# pcb-bldc-high-current.net
KiCad netlist of a schematic drawn in EAGLE
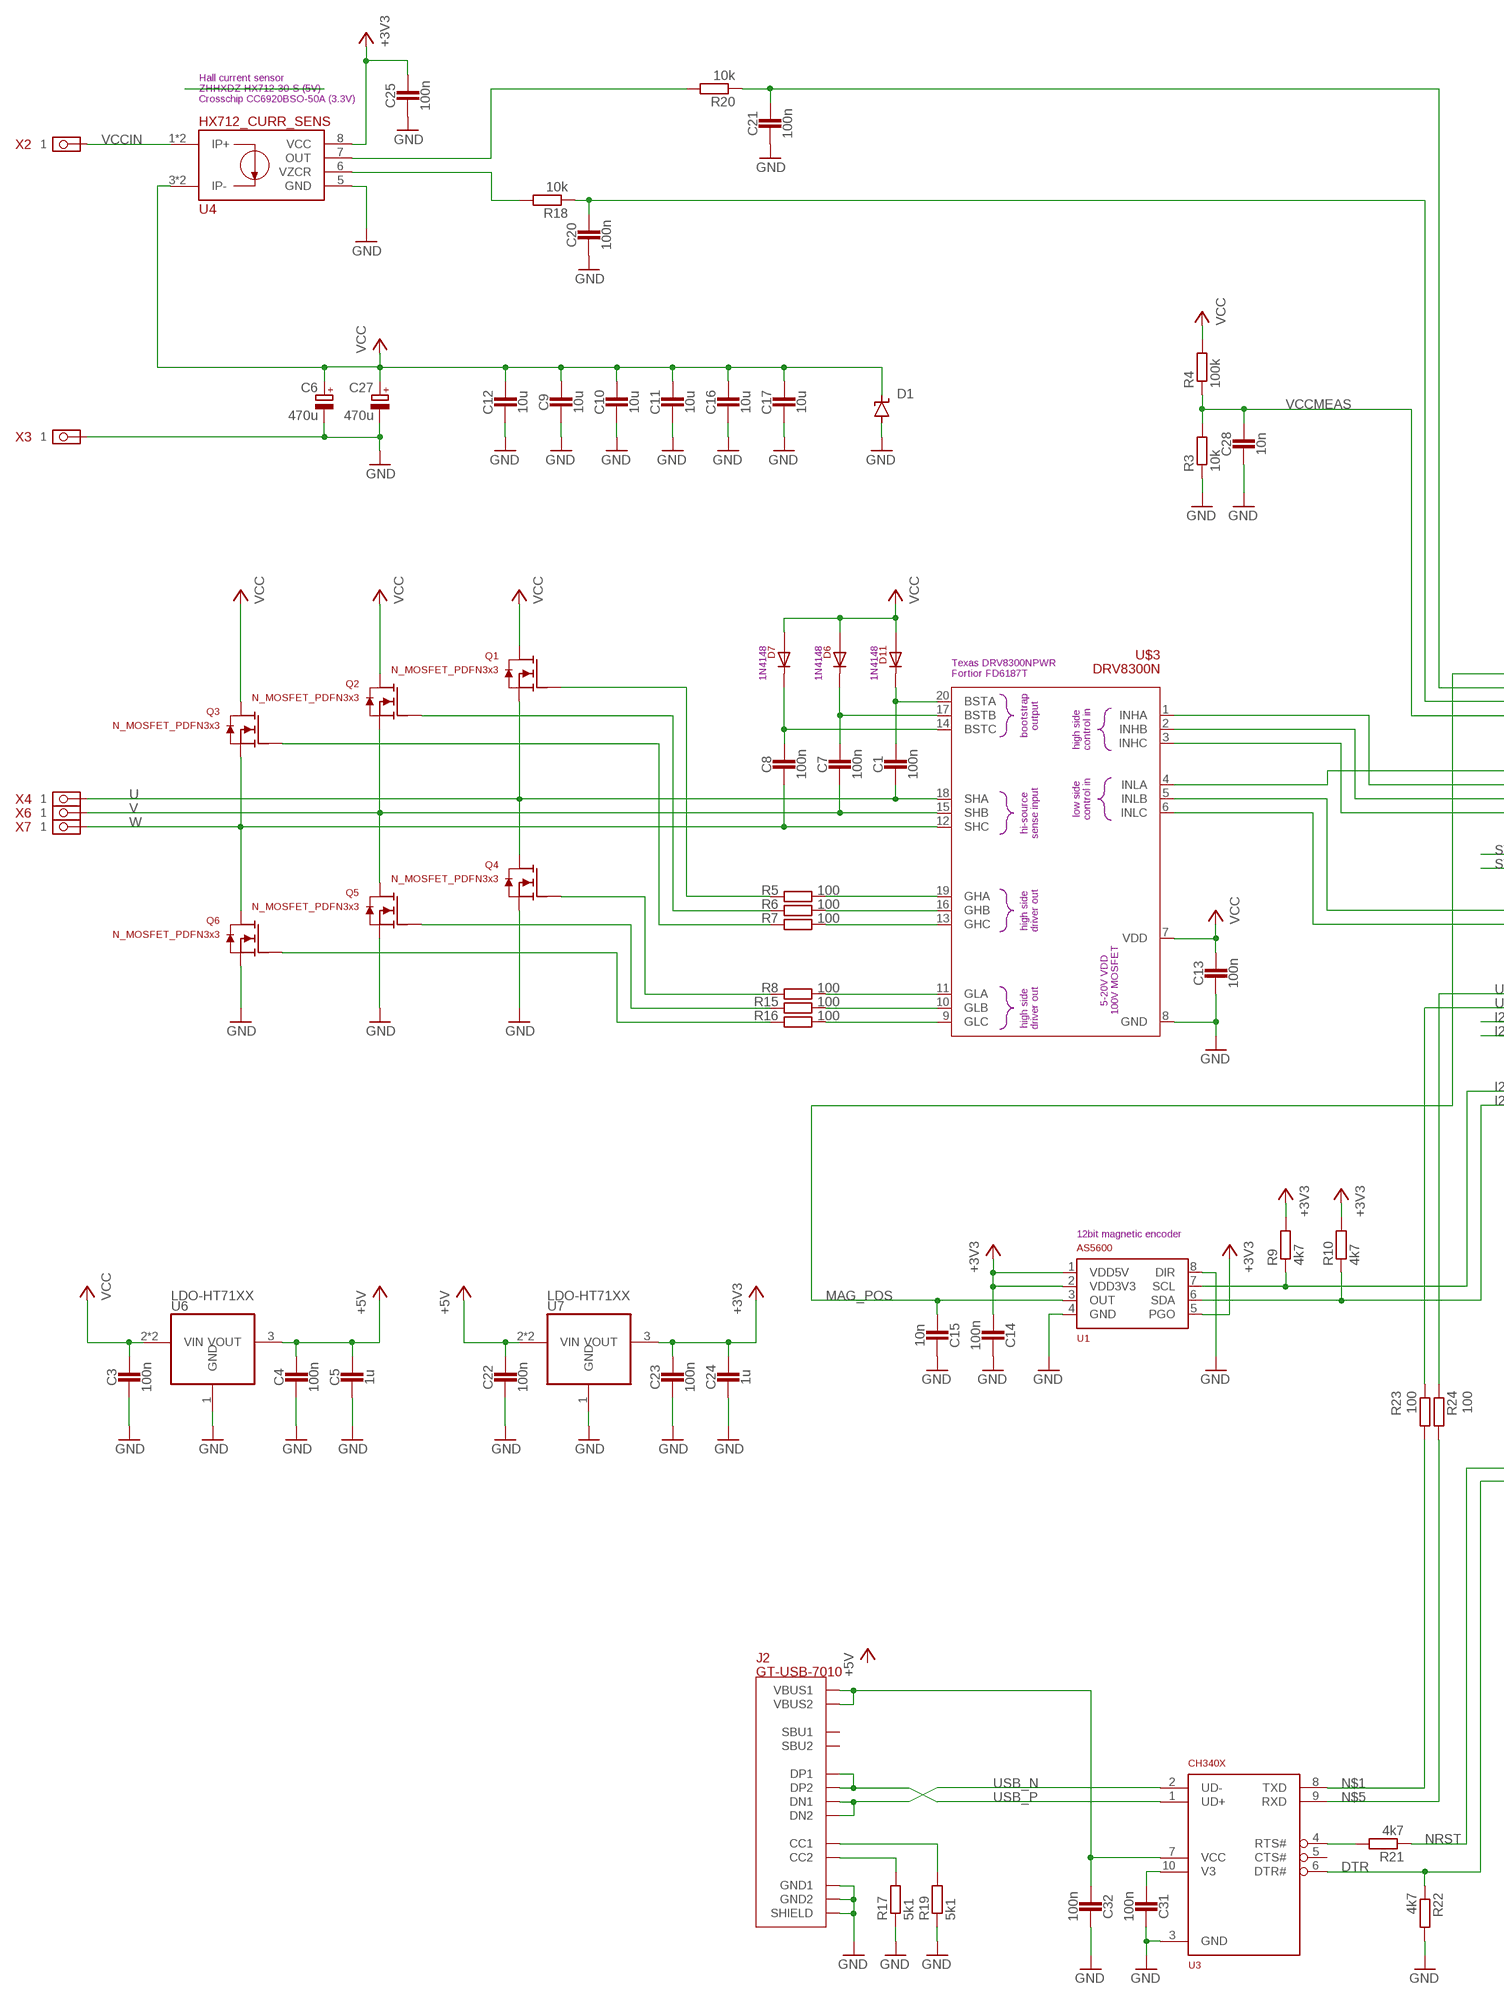
[diagram p0: schematic, sheet 1, part 1 of 2]
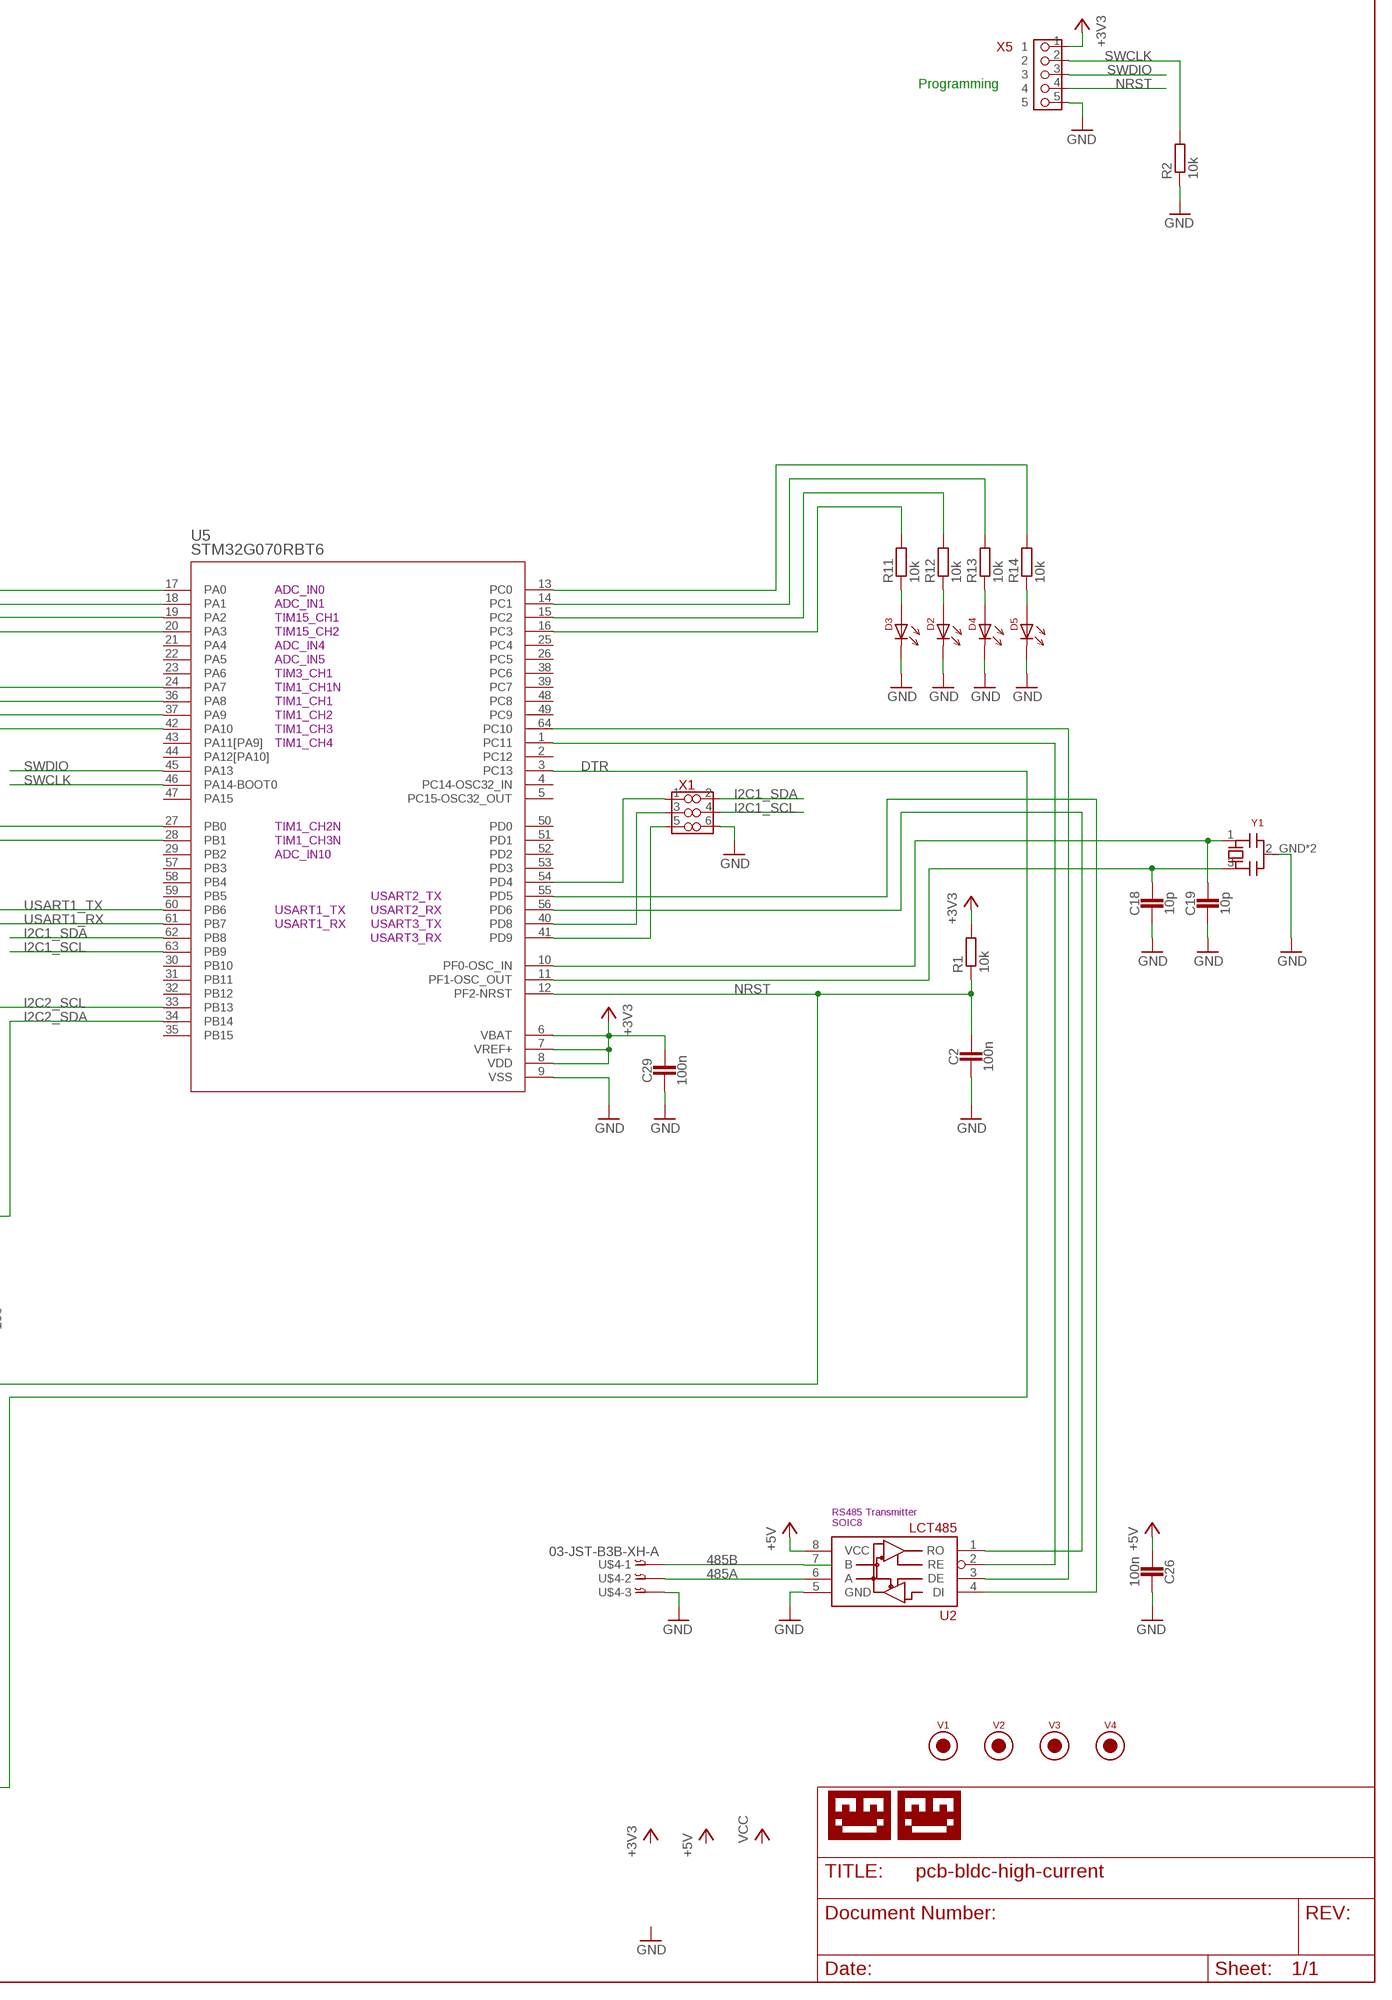
[diagram p1: schematic, sheet 1, part 2 of 2]

(export (version "E")
  (design (tool "Eeschema 10.0.6"))
  (components
    (comp (ref "C1")
      (value "100n")
      (footprint "eagle-import:0603_CAP")
      (libsource (lib "eagle-import") (part "CAPACITOR0603_CAP"))
    )
    (comp (ref "C2")
      (value "100n")
      (footprint "eagle-import:0603_CAP")
      (libsource (lib "eagle-import") (part "CAPACITOR0603_CAP"))
    )
    (comp (ref "C3")
      (value "100n")
      (footprint "eagle-import:0603_CAP")
      (libsource (lib "eagle-import") (part "CAPACITOR0603_CAP"))
    )
    (comp (ref "C4")
      (value "100n")
      (footprint "eagle-import:0603_CAP")
      (libsource (lib "eagle-import") (part "CAPACITOR0603_CAP"))
    )
    (comp (ref "C5")
      (value "1u")
      (footprint "eagle-import:0603_CAP")
      (libsource (lib "eagle-import") (part "CAPACITOR0603_CAP"))
    )
    (comp (ref "C6")
      (value "470u")
      (footprint "eagle-import:153CLV-1010")
      (libsource (lib "eagle-import") (part "CPOL-EU153CLV-1010"))
    )
    (comp (ref "C7")
      (value "100n")
      (footprint "eagle-import:0603_CAP")
      (libsource (lib "eagle-import") (part "CAPACITOR0603_CAP"))
    )
    (comp (ref "C8")
      (value "100n")
      (footprint "eagle-import:0603_CAP")
      (libsource (lib "eagle-import") (part "CAPACITOR0603_CAP"))
    )
    (comp (ref "C9")
      (value "10u")
      (footprint "eagle-import:1206_CAP")
      (libsource (lib "eagle-import") (part "CAPACITOR1206_CAP"))
    )
    (comp (ref "C10")
      (value "10u")
      (footprint "eagle-import:1206_CAP")
      (libsource (lib "eagle-import") (part "CAPACITOR1206_CAP"))
    )
    (comp (ref "C11")
      (value "10u")
      (footprint "eagle-import:1206_CAP")
      (libsource (lib "eagle-import") (part "CAPACITOR1206_CAP"))
    )
    (comp (ref "C12")
      (value "10u")
      (footprint "eagle-import:1206_CAP")
      (libsource (lib "eagle-import") (part "CAPACITOR1206_CAP"))
    )
    (comp (ref "C13")
      (value "100n")
      (footprint "eagle-import:0603_CAP")
      (libsource (lib "eagle-import") (part "CAPACITOR0603_CAP"))
    )
    (comp (ref "C14")
      (value "100n")
      (footprint "eagle-import:0603_CAP")
      (libsource (lib "eagle-import") (part "CAPACITOR0603_CAP"))
    )
    (comp (ref "C15")
      (value "10n")
      (footprint "eagle-import:0603_CAP")
      (libsource (lib "eagle-import") (part "CAPACITOR0603_CAP"))
    )
    (comp (ref "C16")
      (value "10u")
      (footprint "eagle-import:1206_CAP")
      (libsource (lib "eagle-import") (part "CAPACITOR1206_CAP"))
    )
    (comp (ref "C17")
      (value "10u")
      (footprint "eagle-import:1206_CAP")
      (libsource (lib "eagle-import") (part "CAPACITOR1206_CAP"))
    )
    (comp (ref "C18")
      (value "10p")
      (footprint "eagle-import:0603_CAP")
      (libsource (lib "eagle-import") (part "CAPACITOR0603_CAP"))
    )
    (comp (ref "C19")
      (value "10p")
      (footprint "eagle-import:0603_CAP")
      (libsource (lib "eagle-import") (part "CAPACITOR0603_CAP"))
    )
    (comp (ref "C20")
      (value "100n")
      (footprint "eagle-import:0603_CAP")
      (libsource (lib "eagle-import") (part "CAPACITOR0603_CAP"))
    )
    (comp (ref "C21")
      (value "100n")
      (footprint "eagle-import:0603_CAP")
      (libsource (lib "eagle-import") (part "CAPACITOR0603_CAP"))
    )
    (comp (ref "C22")
      (value "100n")
      (footprint "eagle-import:0603_CAP")
      (libsource (lib "eagle-import") (part "CAPACITOR0603_CAP"))
    )
    (comp (ref "C23")
      (value "100n")
      (footprint "eagle-import:0603_CAP")
      (libsource (lib "eagle-import") (part "CAPACITOR0603_CAP"))
    )
    (comp (ref "C24")
      (value "1u")
      (footprint "eagle-import:0603_CAP")
      (libsource (lib "eagle-import") (part "CAPACITOR0603_CAP"))
    )
    (comp (ref "C25")
      (value "100n")
      (footprint "eagle-import:0603_CAP")
      (libsource (lib "eagle-import") (part "CAPACITOR0603_CAP"))
    )
    (comp (ref "C26")
      (value "100n")
      (footprint "eagle-import:0603_CAP")
      (libsource (lib "eagle-import") (part "CAPACITOR0603_CAP"))
    )
    (comp (ref "C27")
      (value "470u")
      (footprint "eagle-import:153CLV-1010")
      (libsource (lib "eagle-import") (part "CPOL-EU153CLV-1010"))
    )
    (comp (ref "C28")
      (value "10n")
      (footprint "eagle-import:0603_CAP")
      (libsource (lib "eagle-import") (part "CAPACITOR0603_CAP"))
    )
    (comp (ref "C29")
      (value "100n")
      (footprint "eagle-import:0603_CAP")
      (libsource (lib "eagle-import") (part "CAPACITOR0603_CAP"))
    )
    (comp (ref "C31")
      (value "100n")
      (footprint "eagle-import:0603_CAP")
      (libsource (lib "eagle-import") (part "CAPACITOR0603_CAP"))
    )
    (comp (ref "C32")
      (value "100n")
      (footprint "eagle-import:0603_CAP")
      (libsource (lib "eagle-import") (part "CAPACITOR0603_CAP"))
    )
    (comp (ref "D1")
      (value "SUPPRESSOR-SMBJ")
      (footprint "eagle-import:SMBJ")
      (libsource (lib "eagle-import") (part "SUPPRESSOR-SMBJ"))
    )
    (comp (ref "D2")
      (value "LED-0805")
      (footprint "eagle-import:0805-DOT")
      (libsource (lib "eagle-import") (part "LED-0805"))
    )
    (comp (ref "D3")
      (value "LED-0805")
      (footprint "eagle-import:0805-DOT")
      (libsource (lib "eagle-import") (part "LED-0805"))
    )
    (comp (ref "D4")
      (value "LED-0805")
      (footprint "eagle-import:0805-DOT")
      (libsource (lib "eagle-import") (part "LED-0805"))
    )
    (comp (ref "D5")
      (value "LED-0805")
      (footprint "eagle-import:0805-DOT")
      (libsource (lib "eagle-import") (part "LED-0805"))
    )
    (comp (ref "D6")
      (value "DIODESOD123")
      (footprint "eagle-import:SOD123")
      (libsource (lib "eagle-import") (part "DIODESOD123"))
    )
    (comp (ref "D7")
      (value "DIODESOD123")
      (footprint "eagle-import:SOD123")
      (libsource (lib "eagle-import") (part "DIODESOD123"))
    )
    (comp (ref "D11")
      (value "DIODESOD123")
      (footprint "eagle-import:SOD123")
      (libsource (lib "eagle-import") (part "DIODESOD123"))
    )
    (comp (ref "J2")
      (value "GT-USB-7010")
      (footprint "eagle-import:GT-USB-7010")
      (libsource (lib "eagle-import") (part "GT-USB-7010"))
    )
    (comp (ref "Q1")
      (value "N_MOSFET_PDFN3x3")
      (footprint "eagle-import:DFN3X3-8L")
      (libsource (lib "eagle-import") (part "MOSFET_NHL60N04D"))
    )
    (comp (ref "Q2")
      (value "N_MOSFET_PDFN3x3")
      (footprint "eagle-import:DFN3X3-8L")
      (libsource (lib "eagle-import") (part "MOSFET_NHL60N04D"))
    )
    (comp (ref "Q3")
      (value "N_MOSFET_PDFN3x3")
      (footprint "eagle-import:DFN3X3-8L")
      (libsource (lib "eagle-import") (part "MOSFET_NHL60N04D"))
    )
    (comp (ref "Q4")
      (value "N_MOSFET_PDFN3x3")
      (footprint "eagle-import:DFN3X3-8L")
      (libsource (lib "eagle-import") (part "MOSFET_NHL60N04D"))
    )
    (comp (ref "Q5")
      (value "N_MOSFET_PDFN3x3")
      (footprint "eagle-import:DFN3X3-8L")
      (libsource (lib "eagle-import") (part "MOSFET_NHL60N04D"))
    )
    (comp (ref "Q6")
      (value "N_MOSFET_PDFN3x3")
      (footprint "eagle-import:DFN3X3-8L")
      (libsource (lib "eagle-import") (part "MOSFET_NHL60N04D"))
    )
    (comp (ref "R1")
      (value "10k")
      (footprint "eagle-import:0603-RES")
      (libsource (lib "eagle-import") (part "RESISTOR0603_RES"))
    )
    (comp (ref "R2")
      (value "10k")
      (footprint "eagle-import:0603-RES")
      (libsource (lib "eagle-import") (part "RESISTOR0603_RES"))
    )
    (comp (ref "R3")
      (value "10k")
      (footprint "eagle-import:0603-RES")
      (libsource (lib "eagle-import") (part "RESISTOR0603_RES"))
    )
    (comp (ref "R4")
      (value "100k")
      (footprint "eagle-import:0603-RES")
      (libsource (lib "eagle-import") (part "RESISTOR0603_RES"))
    )
    (comp (ref "R5")
      (value "100")
      (footprint "eagle-import:0603-RES")
      (libsource (lib "eagle-import") (part "RESISTOR0603_RES"))
    )
    (comp (ref "R6")
      (value "100")
      (footprint "eagle-import:0603-RES")
      (libsource (lib "eagle-import") (part "RESISTOR0603_RES"))
    )
    (comp (ref "R7")
      (value "100")
      (footprint "eagle-import:0603-RES")
      (libsource (lib "eagle-import") (part "RESISTOR0603_RES"))
    )
    (comp (ref "R8")
      (value "100")
      (footprint "eagle-import:0603-RES")
      (libsource (lib "eagle-import") (part "RESISTOR0603_RES"))
    )
    (comp (ref "R9")
      (value "4k7")
      (footprint "eagle-import:0603-RES")
      (libsource (lib "eagle-import") (part "RESISTOR0603_RES"))
    )
    (comp (ref "R10")
      (value "4k7")
      (footprint "eagle-import:0603-RES")
      (libsource (lib "eagle-import") (part "RESISTOR0603_RES"))
    )
    (comp (ref "R11")
      (value "10k")
      (footprint "eagle-import:0603-RES")
      (libsource (lib "eagle-import") (part "RESISTOR0603_RES"))
    )
    (comp (ref "R12")
      (value "10k")
      (footprint "eagle-import:0603-RES")
      (libsource (lib "eagle-import") (part "RESISTOR0603_RES"))
    )
    (comp (ref "R13")
      (value "10k")
      (footprint "eagle-import:0603-RES")
      (libsource (lib "eagle-import") (part "RESISTOR0603_RES"))
    )
    (comp (ref "R14")
      (value "10k")
      (footprint "eagle-import:0603-RES")
      (libsource (lib "eagle-import") (part "RESISTOR0603_RES"))
    )
    (comp (ref "R15")
      (value "100")
      (footprint "eagle-import:0603-RES")
      (libsource (lib "eagle-import") (part "RESISTOR0603_RES"))
    )
    (comp (ref "R16")
      (value "100")
      (footprint "eagle-import:0603-RES")
      (libsource (lib "eagle-import") (part "RESISTOR0603_RES"))
    )
    (comp (ref "R17")
      (value "5k1")
      (footprint "eagle-import:0603-RES")
      (libsource (lib "eagle-import") (part "RESISTOR0603_RES"))
    )
    (comp (ref "R18")
      (value "10k")
      (footprint "eagle-import:0603-RES")
      (libsource (lib "eagle-import") (part "RESISTOR0603_RES"))
    )
    (comp (ref "R19")
      (value "5k1")
      (footprint "eagle-import:0603-RES")
      (libsource (lib "eagle-import") (part "RESISTOR0603_RES"))
    )
    (comp (ref "R20")
      (value "10k")
      (footprint "eagle-import:0603-RES")
      (libsource (lib "eagle-import") (part "RESISTOR0603_RES"))
    )
    (comp (ref "R21")
      (value "4k7")
      (footprint "eagle-import:0603-RES")
      (libsource (lib "eagle-import") (part "RESISTOR0603_RES"))
    )
    (comp (ref "R22")
      (value "4k7")
      (footprint "eagle-import:0603-RES")
      (libsource (lib "eagle-import") (part "RESISTOR0603_RES"))
    )
    (comp (ref "R23")
      (value "100")
      (footprint "eagle-import:0603-RES")
      (libsource (lib "eagle-import") (part "RESISTOR0603_RES"))
    )
    (comp (ref "R24")
      (value "100")
      (footprint "eagle-import:0603-RES")
      (libsource (lib "eagle-import") (part "RESISTOR0603_RES"))
    )
    (comp (ref "U$1")
      (value "LOGO-TOBENG-1MM-FINISH")
      (footprint "eagle-import:TOBENG-1MM-FINISH")
      (libsource (lib "eagle-import") (part "LOGO-TOBENG-1MM-FINISH"))
    )
    (comp (ref "U$2")
      (value "LOGO-0.25MM")
      (footprint "eagle-import:LOGO-0.25MM")
      (libsource (lib "eagle-import") (part "LOGO-0.25MM"))
    )
    (comp (ref "U$3")
      (value "DRV8300N")
      (footprint "eagle-import:TSSOP20")
      (libsource (lib "eagle-import") (part "DRV8300"))
    )
    (comp (ref "U$4")
      (value "03-JST-B3B-XH-A")
      (footprint "eagle-import:B3B-XH")
      (libsource (lib "eagle-import") (part "03-JST-B3B-XH-A"))
    )
    (comp (ref "U1")
      (value "AS5600")
      (footprint "eagle-import:SOIC-8")
      (libsource (lib "eagle-import") (part "AS5600"))
    )
    (comp (ref "U2")
      (value "LCT485_BUS_TRANSCEIVER")
      (footprint "eagle-import:SOIC-8")
      (libsource (lib "eagle-import") (part "LCT485_BUS_TRANSCEIVER"))
    )
    (comp (ref "U3")
      (value "CH340X")
      (footprint "eagle-import:MSOP-10")
      (libsource (lib "eagle-import") (part "CH340X"))
    )
    (comp (ref "U4")
      (value "HX712_CURR_SENS")
      (footprint "eagle-import:SOIC-8")
      (libsource (lib "eagle-import") (part "HX712_CURR_SENS"))
    )
    (comp (ref "U5")
      (value "STM32G070RBT6")
      (footprint "eagle-import:LQFP-64")
      (fields (field (name "COPYRIGHT") "Copyright (C) 2024 Ultra Librarian. All rights reserved."))
      (libsource (lib "eagle-import") (part "STM32G070RBT6"))
    )
    (comp (ref "U6")
      (value "LDO-HT71XX")
      (footprint "eagle-import:SOT-89")
      (libsource (lib "eagle-import") (part "LDO-HT71XX"))
    )
    (comp (ref "U7")
      (value "LDO-HT71XX")
      (footprint "eagle-import:SOT-89")
      (libsource (lib "eagle-import") (part "LDO-HT71XX"))
    )
    (comp (ref "V1")
      (value "FIDUCIAL2MM")
      (footprint "eagle-import:FIDUCIAL_2MM")
      (libsource (lib "eagle-import") (part "FIDUCIAL2MM"))
    )
    (comp (ref "V2")
      (value "FIDUCIAL2MM")
      (footprint "eagle-import:FIDUCIAL_2MM")
      (libsource (lib "eagle-import") (part "FIDUCIAL2MM"))
    )
    (comp (ref "V3")
      (value "FIDUCIAL2MM")
      (footprint "eagle-import:FIDUCIAL_2MM")
      (libsource (lib "eagle-import") (part "FIDUCIAL2MM"))
    )
    (comp (ref "V4")
      (value "FIDUCIAL2MM")
      (footprint "eagle-import:FIDUCIAL_2MM")
      (libsource (lib "eagle-import") (part "FIDUCIAL2MM"))
    )
    (comp (ref "X1")
      (value "PIN_3X2HD")
      (footprint "eagle-import:PIN_3X2_HD")
      (libsource (lib "eagle-import") (part "PIN_3X2HD"))
    )
    (comp (ref "X2")
      (value "PIN_1X1WELDINGTERMINAL")
      (footprint "eagle-import:XFCNTS34031")
      (libsource (lib "eagle-import") (part "PIN_1X1WELDINGTERMINAL"))
    )
    (comp (ref "X3")
      (value "PIN_1X1WELDINGTERMINAL")
      (footprint "eagle-import:XFCNTS34031")
      (libsource (lib "eagle-import") (part "PIN_1X1WELDINGTERMINAL"))
    )
    (comp (ref "X4")
      (value "PIN_1X1WIRE1")
      (footprint "eagle-import:PIN_1X1_SOLDERWIRE_1")
      (libsource (lib "eagle-import") (part "PIN_1X1WIRE1"))
    )
    (comp (ref "X5")
      (value "PIN_5X1HD")
      (footprint "eagle-import:PIN_5X1_HD")
      (libsource (lib "eagle-import") (part "PIN_5X1HD"))
    )
    (comp (ref "X6")
      (value "PIN_1X1WIRE1")
      (footprint "eagle-import:PIN_1X1_SOLDERWIRE_1")
      (libsource (lib "eagle-import") (part "PIN_1X1WIRE1"))
    )
    (comp (ref "X7")
      (value "PIN_1X1WIRE1")
      (footprint "eagle-import:PIN_1X1_SOLDERWIRE_1")
      (libsource (lib "eagle-import") (part "PIN_1X1WIRE1"))
    )
    (comp (ref "Y1")
      (value "3213-QUARZ3225")
      (footprint "eagle-import:3225-QUARZ")
      (libsource (lib "eagle-import") (part "3213-QUARZ3225"))
    )
  )
  (nets
    (net (code "1") (name "+3V3") (class "Default")
      (node (ref "C14") (pin "1") (pinfunction "1_1") (pintype "bidirectional"))
      (node (ref "C23") (pin "1") (pinfunction "1_1") (pintype "bidirectional"))
      (node (ref "C24") (pin "1") (pinfunction "1_1") (pintype "bidirectional"))
      (node (ref "C25") (pin "1") (pinfunction "1_1") (pintype "bidirectional"))
      (node (ref "C29") (pin "1") (pinfunction "1_1") (pintype "bidirectional"))
      (node (ref "R1") (pin "2") (pinfunction "2_2") (pintype "passive"))
      (node (ref "R10") (pin "2") (pinfunction "2_2") (pintype "passive"))
      (node (ref "R9") (pin "2") (pinfunction "2_2") (pintype "passive"))
      (node (ref "U1") (pin "1") (pinfunction "VDD5V_1") (pintype "bidirectional"))
      (node (ref "U1") (pin "2") (pinfunction "VDD3V3_2") (pintype "bidirectional"))
      (node (ref "U1") (pin "5") (pinfunction "PGO_5") (pintype "bidirectional"))
      (node (ref "U4") (pin "8") (pinfunction "VCC_8") (pintype "bidirectional"))
      (node (ref "U5") (pin "6") (pinfunction "VBAT_6") (pintype "power_in"))
      (node (ref "U5") (pin "7") (pinfunction "VREF+_7") (pintype "power_in"))
      (node (ref "U5") (pin "8") (pinfunction "VDD_8") (pintype "power_in"))
      (node (ref "U7") (pin "3") (pinfunction "VOUT_3") (pintype "output"))
      (node (ref "X5") (pin "1") (pinfunction "1_1") (pintype "bidirectional"))
    )
    (net (code "2") (name "+5V") (class "Default")
      (node (ref "C22") (pin "1") (pinfunction "1_1") (pintype "bidirectional"))
      (node (ref "C26") (pin "1") (pinfunction "1_1") (pintype "bidirectional"))
      (node (ref "C4") (pin "1") (pinfunction "1_1") (pintype "bidirectional"))
      (node (ref "C5") (pin "1") (pinfunction "1_1") (pintype "bidirectional"))
      (node (ref "U2") (pin "8") (pinfunction "VCC_8") (pintype "bidirectional"))
      (node (ref "U6") (pin "3") (pinfunction "VOUT_3") (pintype "output"))
      (node (ref "U7") (pin "2") (pinfunction "VIN_2") (pintype "input"))
      (node (ref "U7") (pin "2@1") (pinfunction "VIN_2@1") (pintype "input"))
    )
    (net (code "3") (name "/485A") (class "Default")
      (node (ref "U$4") (pin "P$2") (pinfunction "1_P$2") (pintype "passive"))
      (node (ref "U2") (pin "6") (pinfunction "A_6") (pintype "bidirectional"))
    )
    (net (code "4") (name "/485B") (class "Default")
      (node (ref "U$4") (pin "P$1") (pinfunction "1_P$1") (pintype "passive"))
      (node (ref "U2") (pin "7") (pinfunction "B_7") (pintype "bidirectional"))
    )
    (net (code "5") (name "/DTR") (class "Default")
      (node (ref "R22") (pin "1") (pinfunction "1_1") (pintype "passive"))
      (node (ref "U3") (pin "6") (pinfunction "DTR#_6") (pintype "bidirectional"))
      (node (ref "U5") (pin "3") (pinfunction "PC13_3") (pintype "bidirectional"))
    )
    (net (code "6") (name "/I2C1_SCL") (class "Default")
      (node (ref "U5") (pin "63") (pinfunction "PB9_63") (pintype "bidirectional"))
      (node (ref "X1") (pin "4") (pinfunction "4_4") (pintype "bidirectional"))
    )
    (net (code "7") (name "/I2C1_SDA") (class "Default")
      (node (ref "U5") (pin "62") (pinfunction "PB8_62") (pintype "bidirectional"))
      (node (ref "X1") (pin "2") (pinfunction "2_2") (pintype "bidirectional"))
    )
    (net (code "8") (name "/I2C2_SCL") (class "Default")
      (node (ref "R9") (pin "1") (pinfunction "1_1") (pintype "passive"))
      (node (ref "U1") (pin "7") (pinfunction "SCL_7") (pintype "bidirectional"))
      (node (ref "U5") (pin "33") (pinfunction "PB13_33") (pintype "bidirectional"))
    )
    (net (code "9") (name "/I2C2_SDA") (class "Default")
      (node (ref "R10") (pin "1") (pinfunction "1_1") (pintype "passive"))
      (node (ref "U1") (pin "6") (pinfunction "SDA_6") (pintype "bidirectional"))
      (node (ref "U5") (pin "34") (pinfunction "PB14_34") (pintype "bidirectional"))
    )
    (net (code "10") (name "/MAG_POS") (class "Default")
      (node (ref "C15") (pin "1") (pinfunction "1_1") (pintype "bidirectional"))
      (node (ref "U1") (pin "3") (pinfunction "OUT_3") (pintype "bidirectional"))
      (node (ref "U5") (pin "17") (pinfunction "PA0_17") (pintype "bidirectional"))
    )
    (net (code "11") (name "/N$1") (class "Default")
      (node (ref "R23") (pin "2") (pinfunction "2_2") (pintype "passive"))
      (node (ref "U3") (pin "8") (pinfunction "TXD_8") (pintype "bidirectional"))
    )
    (net (code "12") (name "/N$5") (class "Default")
      (node (ref "R24") (pin "2") (pinfunction "2_2") (pintype "passive"))
      (node (ref "U3") (pin "9") (pinfunction "RXD_9") (pintype "bidirectional"))
    )
    (net (code "13") (name "/NRST") (class "Default")
      (node (ref "C2") (pin "1") (pinfunction "1_1") (pintype "bidirectional"))
      (node (ref "R1") (pin "1") (pinfunction "1_1") (pintype "passive"))
      (node (ref "R21") (pin "1") (pinfunction "1_1") (pintype "passive"))
      (node (ref "U5") (pin "12") (pinfunction "PF2-NRST_12") (pintype "bidirectional"))
      (node (ref "X5") (pin "4") (pinfunction "4_4") (pintype "bidirectional"))
    )
    (net (code "14") (name "/SWCLK") (class "Default")
      (node (ref "R2") (pin "2") (pinfunction "2_2") (pintype "passive"))
      (node (ref "U5") (pin "46") (pinfunction "PA14-BOOT0_46") (pintype "bidirectional"))
      (node (ref "X5") (pin "2") (pinfunction "2_2") (pintype "bidirectional"))
    )
    (net (code "15") (name "/SWDIO") (class "Default")
      (node (ref "U5") (pin "45") (pinfunction "PA13_45") (pintype "bidirectional"))
      (node (ref "X5") (pin "3") (pinfunction "3_3") (pintype "bidirectional"))
    )
    (net (code "16") (name "/U") (class "Default")
      (node (ref "C1") (pin "2") (pinfunction "2_2") (pintype "bidirectional"))
      (node (ref "Q1") (pin "S1") (pinfunction "S_S1") (pintype "bidirectional"))
      (node (ref "Q1") (pin "S2") (pinfunction "S_S2") (pintype "bidirectional"))
      (node (ref "Q1") (pin "S3") (pinfunction "S_S3") (pintype "bidirectional"))
      (node (ref "Q4") (pin "D") (pinfunction "D_D") (pintype "bidirectional"))
      (node (ref "U$3") (pin "18") (pinfunction "SHA_18") (pintype "bidirectional"))
      (node (ref "X4") (pin "P$1") (pinfunction "1_P$1") (pintype "bidirectional"))
      (node (ref "X4") (pin "P$10") (pinfunction "1_P$10") (pintype "bidirectional"))
      (node (ref "X4") (pin "P$11") (pinfunction "1_P$11") (pintype "bidirectional"))
      (node (ref "X4") (pin "P$12") (pinfunction "1_P$12") (pintype "bidirectional"))
      (node (ref "X4") (pin "P$13") (pinfunction "1_P$13") (pintype "bidirectional"))
      (node (ref "X4") (pin "P$14") (pinfunction "1_P$14") (pintype "bidirectional"))
      (node (ref "X4") (pin "P$15") (pinfunction "1_P$15") (pintype "bidirectional"))
      (node (ref "X4") (pin "P$16") (pinfunction "1_P$16") (pintype "bidirectional"))
      (node (ref "X4") (pin "P$17") (pinfunction "1_P$17") (pintype "bidirectional"))
      (node (ref "X4") (pin "P$18") (pinfunction "1_P$18") (pintype "bidirectional"))
      (node (ref "X4") (pin "P$19") (pinfunction "1_P$19") (pintype "bidirectional"))
      (node (ref "X4") (pin "P$2") (pinfunction "1_P$2") (pintype "bidirectional"))
      (node (ref "X4") (pin "P$20") (pinfunction "1_P$20") (pintype "bidirectional"))
      (node (ref "X4") (pin "P$3") (pinfunction "1_P$3") (pintype "bidirectional"))
      (node (ref "X4") (pin "P$4") (pinfunction "1_P$4") (pintype "bidirectional"))
      (node (ref "X4") (pin "P$5") (pinfunction "1_P$5") (pintype "bidirectional"))
      (node (ref "X4") (pin "P$6") (pinfunction "1_P$6") (pintype "bidirectional"))
      (node (ref "X4") (pin "P$7") (pinfunction "1_P$7") (pintype "bidirectional"))
      (node (ref "X4") (pin "P$8") (pinfunction "1_P$8") (pintype "bidirectional"))
      (node (ref "X4") (pin "P$9") (pinfunction "1_P$9") (pintype "bidirectional"))
    )
    (net (code "17") (name "/USART1_RX") (class "Default")
      (node (ref "R23") (pin "1") (pinfunction "1_1") (pintype "passive"))
      (node (ref "U5") (pin "61") (pinfunction "PB7_61") (pintype "bidirectional"))
    )
    (net (code "18") (name "/USART1_TX") (class "Default")
      (node (ref "R24") (pin "1") (pinfunction "1_1") (pintype "passive"))
      (node (ref "U5") (pin "60") (pinfunction "PB6_60") (pintype "bidirectional"))
    )
    (net (code "19") (name "/USB_N") (class "Default")
      (node (ref "J2") (pin "A7") (pinfunction "DN1_A7") (pintype "bidirectional"))
      (node (ref "J2") (pin "B7") (pinfunction "DN2_B7") (pintype "bidirectional"))
      (node (ref "U3") (pin "2") (pinfunction "UD-_2") (pintype "bidirectional"))
    )
    (net (code "20") (name "/USB_P") (class "Default")
      (node (ref "J2") (pin "A6") (pinfunction "DP1_A6") (pintype "bidirectional"))
      (node (ref "J2") (pin "B6") (pinfunction "DP2_B6") (pintype "bidirectional"))
      (node (ref "U3") (pin "1") (pinfunction "UD+_1") (pintype "bidirectional"))
    )
    (net (code "21") (name "/V") (class "Default")
      (node (ref "C7") (pin "2") (pinfunction "2_2") (pintype "bidirectional"))
      (node (ref "Q2") (pin "S1") (pinfunction "S_S1") (pintype "bidirectional"))
      (node (ref "Q2") (pin "S2") (pinfunction "S_S2") (pintype "bidirectional"))
      (node (ref "Q2") (pin "S3") (pinfunction "S_S3") (pintype "bidirectional"))
      (node (ref "Q5") (pin "D") (pinfunction "D_D") (pintype "bidirectional"))
      (node (ref "U$3") (pin "15") (pinfunction "SHB_15") (pintype "bidirectional"))
      (node (ref "X6") (pin "P$1") (pinfunction "1_P$1") (pintype "bidirectional"))
      (node (ref "X6") (pin "P$10") (pinfunction "1_P$10") (pintype "bidirectional"))
      (node (ref "X6") (pin "P$11") (pinfunction "1_P$11") (pintype "bidirectional"))
      (node (ref "X6") (pin "P$12") (pinfunction "1_P$12") (pintype "bidirectional"))
      (node (ref "X6") (pin "P$13") (pinfunction "1_P$13") (pintype "bidirectional"))
      (node (ref "X6") (pin "P$14") (pinfunction "1_P$14") (pintype "bidirectional"))
      (node (ref "X6") (pin "P$15") (pinfunction "1_P$15") (pintype "bidirectional"))
      (node (ref "X6") (pin "P$16") (pinfunction "1_P$16") (pintype "bidirectional"))
      (node (ref "X6") (pin "P$17") (pinfunction "1_P$17") (pintype "bidirectional"))
      (node (ref "X6") (pin "P$18") (pinfunction "1_P$18") (pintype "bidirectional"))
      (node (ref "X6") (pin "P$19") (pinfunction "1_P$19") (pintype "bidirectional"))
      (node (ref "X6") (pin "P$2") (pinfunction "1_P$2") (pintype "bidirectional"))
      (node (ref "X6") (pin "P$20") (pinfunction "1_P$20") (pintype "bidirectional"))
      (node (ref "X6") (pin "P$3") (pinfunction "1_P$3") (pintype "bidirectional"))
      (node (ref "X6") (pin "P$4") (pinfunction "1_P$4") (pintype "bidirectional"))
      (node (ref "X6") (pin "P$5") (pinfunction "1_P$5") (pintype "bidirectional"))
      (node (ref "X6") (pin "P$6") (pinfunction "1_P$6") (pintype "bidirectional"))
      (node (ref "X6") (pin "P$7") (pinfunction "1_P$7") (pintype "bidirectional"))
      (node (ref "X6") (pin "P$8") (pinfunction "1_P$8") (pintype "bidirectional"))
      (node (ref "X6") (pin "P$9") (pinfunction "1_P$9") (pintype "bidirectional"))
    )
    (net (code "22") (name "/VCCIN") (class "Default")
      (node (ref "U4") (pin "1") (pinfunction "IP+_1") (pintype "bidirectional"))
      (node (ref "U4") (pin "2") (pinfunction "IP+_2") (pintype "bidirectional"))
      (node (ref "X2") (pin "1") (pinfunction "1_1") (pintype "bidirectional"))
      (node (ref "X2") (pin "2") (pinfunction "1_2") (pintype "bidirectional"))
      (node (ref "X2") (pin "3") (pinfunction "1_3") (pintype "bidirectional"))
      (node (ref "X2") (pin "4") (pinfunction "1_4") (pintype "bidirectional"))
    )
    (net (code "23") (name "/VCCMEAS") (class "Default")
      (node (ref "C28") (pin "1") (pinfunction "1_1") (pintype "bidirectional"))
      (node (ref "R3") (pin "2") (pinfunction "2_2") (pintype "passive"))
      (node (ref "R4") (pin "1") (pinfunction "1_1") (pintype "passive"))
      (node (ref "U5") (pin "20") (pinfunction "PA3_20") (pintype "bidirectional"))
    )
    (net (code "24") (name "/W") (class "Default")
      (node (ref "C8") (pin "2") (pinfunction "2_2") (pintype "bidirectional"))
      (node (ref "Q3") (pin "S1") (pinfunction "S_S1") (pintype "bidirectional"))
      (node (ref "Q3") (pin "S2") (pinfunction "S_S2") (pintype "bidirectional"))
      (node (ref "Q3") (pin "S3") (pinfunction "S_S3") (pintype "bidirectional"))
      (node (ref "Q6") (pin "D") (pinfunction "D_D") (pintype "bidirectional"))
      (node (ref "U$3") (pin "12") (pinfunction "SHC_12") (pintype "bidirectional"))
      (node (ref "X7") (pin "P$1") (pinfunction "1_P$1") (pintype "bidirectional"))
      (node (ref "X7") (pin "P$10") (pinfunction "1_P$10") (pintype "bidirectional"))
      (node (ref "X7") (pin "P$11") (pinfunction "1_P$11") (pintype "bidirectional"))
      (node (ref "X7") (pin "P$12") (pinfunction "1_P$12") (pintype "bidirectional"))
      (node (ref "X7") (pin "P$13") (pinfunction "1_P$13") (pintype "bidirectional"))
      (node (ref "X7") (pin "P$14") (pinfunction "1_P$14") (pintype "bidirectional"))
      (node (ref "X7") (pin "P$15") (pinfunction "1_P$15") (pintype "bidirectional"))
      (node (ref "X7") (pin "P$16") (pinfunction "1_P$16") (pintype "bidirectional"))
      (node (ref "X7") (pin "P$17") (pinfunction "1_P$17") (pintype "bidirectional"))
      (node (ref "X7") (pin "P$18") (pinfunction "1_P$18") (pintype "bidirectional"))
      (node (ref "X7") (pin "P$19") (pinfunction "1_P$19") (pintype "bidirectional"))
      (node (ref "X7") (pin "P$2") (pinfunction "1_P$2") (pintype "bidirectional"))
      (node (ref "X7") (pin "P$20") (pinfunction "1_P$20") (pintype "bidirectional"))
      (node (ref "X7") (pin "P$3") (pinfunction "1_P$3") (pintype "bidirectional"))
      (node (ref "X7") (pin "P$4") (pinfunction "1_P$4") (pintype "bidirectional"))
      (node (ref "X7") (pin "P$5") (pinfunction "1_P$5") (pintype "bidirectional"))
      (node (ref "X7") (pin "P$6") (pinfunction "1_P$6") (pintype "bidirectional"))
      (node (ref "X7") (pin "P$7") (pinfunction "1_P$7") (pintype "bidirectional"))
      (node (ref "X7") (pin "P$8") (pinfunction "1_P$8") (pintype "bidirectional"))
      (node (ref "X7") (pin "P$9") (pinfunction "1_P$9") (pintype "bidirectional"))
    )
    (net (code "25") (name "GND") (class "Default")
      (node (ref "C10") (pin "2") (pinfunction "2_2") (pintype "bidirectional"))
      (node (ref "C11") (pin "2") (pinfunction "2_2") (pintype "bidirectional"))
      (node (ref "C12") (pin "2") (pinfunction "2_2") (pintype "bidirectional"))
      (node (ref "C13") (pin "2") (pinfunction "2_2") (pintype "bidirectional"))
      (node (ref "C14") (pin "2") (pinfunction "2_2") (pintype "bidirectional"))
      (node (ref "C15") (pin "2") (pinfunction "2_2") (pintype "bidirectional"))
      (node (ref "C16") (pin "2") (pinfunction "2_2") (pintype "bidirectional"))
      (node (ref "C17") (pin "2") (pinfunction "2_2") (pintype "bidirectional"))
      (node (ref "C18") (pin "2") (pinfunction "2_2") (pintype "bidirectional"))
      (node (ref "C19") (pin "2") (pinfunction "2_2") (pintype "bidirectional"))
      (node (ref "C2") (pin "2") (pinfunction "2_2") (pintype "bidirectional"))
      (node (ref "C20") (pin "2") (pinfunction "2_2") (pintype "bidirectional"))
      (node (ref "C21") (pin "2") (pinfunction "2_2") (pintype "bidirectional"))
      (node (ref "C22") (pin "2") (pinfunction "2_2") (pintype "bidirectional"))
      (node (ref "C23") (pin "2") (pinfunction "2_2") (pintype "bidirectional"))
      (node (ref "C24") (pin "2") (pinfunction "2_2") (pintype "bidirectional"))
      (node (ref "C25") (pin "2") (pinfunction "2_2") (pintype "bidirectional"))
      (node (ref "C26") (pin "2") (pinfunction "2_2") (pintype "bidirectional"))
      (node (ref "C27") (pin "-") (pinfunction "-_-") (pintype "passive"))
      (node (ref "C28") (pin "2") (pinfunction "2_2") (pintype "bidirectional"))
      (node (ref "C29") (pin "2") (pinfunction "2_2") (pintype "bidirectional"))
      (node (ref "C3") (pin "2") (pinfunction "2_2") (pintype "bidirectional"))
      (node (ref "C31") (pin "2") (pinfunction "2_2") (pintype "bidirectional"))
      (node (ref "C32") (pin "2") (pinfunction "2_2") (pintype "bidirectional"))
      (node (ref "C4") (pin "2") (pinfunction "2_2") (pintype "bidirectional"))
      (node (ref "C5") (pin "2") (pinfunction "2_2") (pintype "bidirectional"))
      (node (ref "C6") (pin "-") (pinfunction "-_-") (pintype "passive"))
      (node (ref "C9") (pin "2") (pinfunction "2_2") (pintype "bidirectional"))
      (node (ref "D1") (pin "A") (pinfunction "A_A") (pintype "passive"))
      (node (ref "D2") (pin "2") (pinfunction "2_2") (pintype "bidirectional"))
      (node (ref "D3") (pin "2") (pinfunction "2_2") (pintype "bidirectional"))
      (node (ref "D4") (pin "2") (pinfunction "2_2") (pintype "bidirectional"))
      (node (ref "D5") (pin "2") (pinfunction "2_2") (pintype "bidirectional"))
      (node (ref "J2") (pin "13") (pinfunction "SHIELD_13") (pintype "bidirectional"))
      (node (ref "J2") (pin "14") (pinfunction "SHIELD_14") (pintype "bidirectional"))
      (node (ref "J2") (pin "15") (pinfunction "SHIELD_15") (pintype "bidirectional"))
      (node (ref "J2") (pin "16") (pinfunction "SHIELD_16") (pintype "bidirectional"))
      (node (ref "J2") (pin "A1B12") (pinfunction "GND1_A1B12") (pintype "bidirectional"))
      (node (ref "J2") (pin "B1A12") (pinfunction "GND2_B1A12") (pintype "bidirectional"))
      (node (ref "J2") (pin "PAD1") (pinfunction "SHIELD_PAD1") (pintype "bidirectional"))
      (node (ref "J2") (pin "PAD2") (pinfunction "SHIELD_PAD2") (pintype "bidirectional"))
      (node (ref "J2") (pin "PAD3") (pinfunction "SHIELD_PAD3") (pintype "bidirectional"))
      (node (ref "J2") (pin "PAD4") (pinfunction "SHIELD_PAD4") (pintype "bidirectional"))
      (node (ref "J2") (pin "PAD5") (pinfunction "SHIELD_PAD5") (pintype "bidirectional"))
      (node (ref "J2") (pin "PAD6") (pinfunction "SHIELD_PAD6") (pintype "bidirectional"))
      (node (ref "Q4") (pin "S1") (pinfunction "S_S1") (pintype "bidirectional"))
      (node (ref "Q4") (pin "S2") (pinfunction "S_S2") (pintype "bidirectional"))
      (node (ref "Q4") (pin "S3") (pinfunction "S_S3") (pintype "bidirectional"))
      (node (ref "Q5") (pin "S1") (pinfunction "S_S1") (pintype "bidirectional"))
      (node (ref "Q5") (pin "S2") (pinfunction "S_S2") (pintype "bidirectional"))
      (node (ref "Q5") (pin "S3") (pinfunction "S_S3") (pintype "bidirectional"))
      (node (ref "Q6") (pin "S1") (pinfunction "S_S1") (pintype "bidirectional"))
      (node (ref "Q6") (pin "S2") (pinfunction "S_S2") (pintype "bidirectional"))
      (node (ref "Q6") (pin "S3") (pinfunction "S_S3") (pintype "bidirectional"))
      (node (ref "R17") (pin "1") (pinfunction "1_1") (pintype "passive"))
      (node (ref "R19") (pin "1") (pinfunction "1_1") (pintype "passive"))
      (node (ref "R2") (pin "1") (pinfunction "1_1") (pintype "passive"))
      (node (ref "R22") (pin "2") (pinfunction "2_2") (pintype "passive"))
      (node (ref "R3") (pin "1") (pinfunction "1_1") (pintype "passive"))
      (node (ref "U$3") (pin "8") (pinfunction "GND_8") (pintype "bidirectional"))
      (node (ref "U$4") (pin "P$3") (pinfunction "1_P$3") (pintype "passive"))
      (node (ref "U1") (pin "4") (pinfunction "GND_4") (pintype "bidirectional"))
      (node (ref "U1") (pin "8") (pinfunction "DIR_8") (pintype "bidirectional"))
      (node (ref "U2") (pin "5") (pinfunction "GND_5") (pintype "bidirectional"))
      (node (ref "U3") (pin "3") (pinfunction "GND_3") (pintype "bidirectional"))
      (node (ref "U4") (pin "5") (pinfunction "GND_5") (pintype "bidirectional"))
      (node (ref "U5") (pin "9") (pinfunction "VSS_9") (pintype "power_in"))
      (node (ref "U6") (pin "1") (pinfunction "GND_1") (pintype "power_in"))
      (node (ref "U7") (pin "1") (pinfunction "GND_1") (pintype "power_in"))
      (node (ref "X1") (pin "6") (pinfunction "6_6") (pintype "bidirectional"))
      (node (ref "X3") (pin "1") (pinfunction "1_1") (pintype "bidirectional"))
      (node (ref "X3") (pin "2") (pinfunction "1_2") (pintype "bidirectional"))
      (node (ref "X3") (pin "3") (pinfunction "1_3") (pintype "bidirectional"))
      (node (ref "X3") (pin "4") (pinfunction "1_4") (pintype "bidirectional"))
      (node (ref "X5") (pin "5") (pinfunction "5_5") (pintype "bidirectional"))
      (node (ref "Y1") (pin "2_GND") (pinfunction "2_2_GND") (pintype "bidirectional"))
      (node (ref "Y1") (pin "4_GND") (pinfunction "2_4_GND") (pintype "bidirectional"))
    )
    (net (code "26") (name "Net-(D2-Pad1)") (class "Default")
      (node (ref "D2") (pin "1") (pinfunction "1_1") (pintype "bidirectional"))
      (node (ref "R12") (pin "1") (pinfunction "1_1") (pintype "passive"))
    )
    (net (code "27") (name "Net-(D3-Pad1)") (class "Default")
      (node (ref "D3") (pin "1") (pinfunction "1_1") (pintype "bidirectional"))
      (node (ref "R11") (pin "1") (pinfunction "1_1") (pintype "passive"))
    )
    (net (code "28") (name "Net-(D4-Pad1)") (class "Default")
      (node (ref "D4") (pin "1") (pinfunction "1_1") (pintype "bidirectional"))
      (node (ref "R13") (pin "1") (pinfunction "1_1") (pintype "passive"))
    )
    (net (code "29") (name "Net-(D5-Pad1)") (class "Default")
      (node (ref "D5") (pin "1") (pinfunction "1_1") (pintype "bidirectional"))
      (node (ref "R14") (pin "1") (pinfunction "1_1") (pintype "passive"))
    )
    (net (code "30") (name "Net-(D6-2)") (class "Default")
      (node (ref "C7") (pin "1") (pinfunction "1_1") (pintype "bidirectional"))
      (node (ref "D6") (pin "C") (pinfunction "2_C") (pintype "bidirectional"))
      (node (ref "U$3") (pin "17") (pinfunction "BSTB_17") (pintype "bidirectional"))
    )
    (net (code "31") (name "Net-(D7-2)") (class "Default")
      (node (ref "C8") (pin "1") (pinfunction "1_1") (pintype "bidirectional"))
      (node (ref "D7") (pin "C") (pinfunction "2_C") (pintype "bidirectional"))
      (node (ref "U$3") (pin "14") (pinfunction "BSTC_14") (pintype "bidirectional"))
    )
    (net (code "32") (name "Net-(D11-2)") (class "Default")
      (node (ref "C1") (pin "1") (pinfunction "1_1") (pintype "bidirectional"))
      (node (ref "D11") (pin "C") (pinfunction "2_C") (pintype "bidirectional"))
      (node (ref "U$3") (pin "20") (pinfunction "BSTA_20") (pintype "bidirectional"))
    )
    (net (code "33") (name "Net-(J2-CC1)") (class "Default")
      (node (ref "J2") (pin "A5") (pinfunction "CC1_A5") (pintype "bidirectional"))
      (node (ref "R19") (pin "2") (pinfunction "2_2") (pintype "passive"))
    )
    (net (code "34") (name "Net-(J2-CC2)") (class "Default")
      (node (ref "J2") (pin "B5") (pinfunction "CC2_B5") (pintype "bidirectional"))
      (node (ref "R17") (pin "2") (pinfunction "2_2") (pintype "passive"))
    )
    (net (code "35") (name "Net-(J2-VBUS1)") (class "Default")
      (node (ref "C32") (pin "1") (pinfunction "1_1") (pintype "bidirectional"))
      (node (ref "J2") (pin "A4B9") (pinfunction "VBUS1_A4B9") (pintype "bidirectional"))
      (node (ref "J2") (pin "B4A9") (pinfunction "VBUS2_B4A9") (pintype "bidirectional"))
      (node (ref "U3") (pin "7") (pinfunction "VCC_7") (pintype "bidirectional"))
    )
    (net (code "36") (name "Net-(Q1-PadG)") (class "Default")
      (node (ref "Q1") (pin "G") (pinfunction "G_G") (pintype "bidirectional"))
      (node (ref "R5") (pin "2") (pinfunction "2_2") (pintype "passive"))
    )
    (net (code "37") (name "Net-(Q2-PadG)") (class "Default")
      (node (ref "Q2") (pin "G") (pinfunction "G_G") (pintype "bidirectional"))
      (node (ref "R6") (pin "2") (pinfunction "2_2") (pintype "passive"))
    )
    (net (code "38") (name "Net-(Q3-PadG)") (class "Default")
      (node (ref "Q3") (pin "G") (pinfunction "G_G") (pintype "bidirectional"))
      (node (ref "R7") (pin "2") (pinfunction "2_2") (pintype "passive"))
    )
    (net (code "39") (name "Net-(Q4-PadG)") (class "Default")
      (node (ref "Q4") (pin "G") (pinfunction "G_G") (pintype "bidirectional"))
      (node (ref "R8") (pin "2") (pinfunction "2_2") (pintype "passive"))
    )
    (net (code "40") (name "Net-(Q5-PadG)") (class "Default")
      (node (ref "Q5") (pin "G") (pinfunction "G_G") (pintype "bidirectional"))
      (node (ref "R15") (pin "2") (pinfunction "2_2") (pintype "passive"))
    )
    (net (code "41") (name "Net-(Q6-PadG)") (class "Default")
      (node (ref "Q6") (pin "G") (pinfunction "G_G") (pintype "bidirectional"))
      (node (ref "R16") (pin "2") (pinfunction "2_2") (pintype "passive"))
    )
    (net (code "42") (name "Net-(U$3-GHA)") (class "Default")
      (node (ref "R5") (pin "1") (pinfunction "1_1") (pintype "passive"))
      (node (ref "U$3") (pin "19") (pinfunction "GHA_19") (pintype "bidirectional"))
    )
    (net (code "43") (name "Net-(U$3-GHB)") (class "Default")
      (node (ref "R6") (pin "1") (pinfunction "1_1") (pintype "passive"))
      (node (ref "U$3") (pin "16") (pinfunction "GHB_16") (pintype "bidirectional"))
    )
    (net (code "44") (name "Net-(U$3-GHC)") (class "Default")
      (node (ref "R7") (pin "1") (pinfunction "1_1") (pintype "passive"))
      (node (ref "U$3") (pin "13") (pinfunction "GHC_13") (pintype "bidirectional"))
    )
    (net (code "45") (name "Net-(U$3-GLA)") (class "Default")
      (node (ref "R8") (pin "1") (pinfunction "1_1") (pintype "passive"))
      (node (ref "U$3") (pin "11") (pinfunction "GLA_11") (pintype "bidirectional"))
    )
    (net (code "46") (name "Net-(U$3-GLB)") (class "Default")
      (node (ref "R15") (pin "1") (pinfunction "1_1") (pintype "passive"))
      (node (ref "U$3") (pin "10") (pinfunction "GLB_10") (pintype "bidirectional"))
    )
    (net (code "47") (name "Net-(U$3-GLC)") (class "Default")
      (node (ref "R16") (pin "1") (pinfunction "1_1") (pintype "passive"))
      (node (ref "U$3") (pin "9") (pinfunction "GLC_9") (pintype "bidirectional"))
    )
    (net (code "48") (name "Net-(U$3-INHA)") (class "Default")
      (node (ref "U$3") (pin "1") (pinfunction "INHA_1") (pintype "bidirectional"))
      (node (ref "U5") (pin "36") (pinfunction "PA8_36") (pintype "bidirectional"))
    )
    (net (code "49") (name "Net-(U$3-INHB)") (class "Default")
      (node (ref "U$3") (pin "2") (pinfunction "INHB_2") (pintype "bidirectional"))
      (node (ref "U5") (pin "37") (pinfunction "PA9_37") (pintype "bidirectional"))
    )
    (net (code "50") (name "Net-(U$3-INHC)") (class "Default")
      (node (ref "U$3") (pin "3") (pinfunction "INHC_3") (pintype "bidirectional"))
      (node (ref "U5") (pin "42") (pinfunction "PA10_42") (pintype "bidirectional"))
    )
    (net (code "51") (name "Net-(U$3-INLA)") (class "Default")
      (node (ref "U$3") (pin "4") (pinfunction "INLA_4") (pintype "bidirectional"))
      (node (ref "U5") (pin "24") (pinfunction "PA7_24") (pintype "bidirectional"))
    )
    (net (code "52") (name "Net-(U$3-INLB)") (class "Default")
      (node (ref "U$3") (pin "5") (pinfunction "INLB_5") (pintype "bidirectional"))
      (node (ref "U5") (pin "27") (pinfunction "PB0_27") (pintype "bidirectional"))
    )
    (net (code "53") (name "Net-(U$3-INLC)") (class "Default")
      (node (ref "U$3") (pin "6") (pinfunction "INLC_6") (pintype "bidirectional"))
      (node (ref "U5") (pin "28") (pinfunction "PB1_28") (pintype "bidirectional"))
    )
    (net (code "54") (name "Net-(U2-DE)") (class "Default")
      (node (ref "U2") (pin "3") (pinfunction "DE_3") (pintype "bidirectional"))
      (node (ref "U5") (pin "64") (pinfunction "PC10_64") (pintype "bidirectional"))
    )
    (net (code "55") (name "Net-(U2-DI)") (class "Default")
      (node (ref "U2") (pin "4") (pinfunction "DI_4") (pintype "bidirectional"))
      (node (ref "U5") (pin "55") (pinfunction "PD5_55") (pintype "bidirectional"))
    )
    (net (code "56") (name "Net-(U2-RE)") (class "Default")
      (node (ref "U2") (pin "2") (pinfunction "RE_2") (pintype "bidirectional"))
      (node (ref "U5") (pin "1") (pinfunction "PC11_1") (pintype "bidirectional"))
    )
    (net (code "57") (name "Net-(U2-RO)") (class "Default")
      (node (ref "U2") (pin "1") (pinfunction "RO_1") (pintype "bidirectional"))
      (node (ref "U5") (pin "56") (pinfunction "PD6_56") (pintype "bidirectional"))
    )
    (net (code "58") (name "Net-(U3-RTS#)") (class "Default")
      (node (ref "R21") (pin "2") (pinfunction "2_2") (pintype "passive"))
      (node (ref "U3") (pin "4") (pinfunction "RTS#_4") (pintype "bidirectional"))
    )
    (net (code "59") (name "Net-(U3-V3)") (class "Default")
      (node (ref "C31") (pin "1") (pinfunction "1_1") (pintype "bidirectional"))
      (node (ref "U3") (pin "10") (pinfunction "V3_10") (pintype "bidirectional"))
    )
    (net (code "60") (name "Net-(U4-OUT)") (class "Default")
      (node (ref "R20") (pin "2") (pinfunction "2_2") (pintype "passive"))
      (node (ref "U4") (pin "7") (pinfunction "OUT_7") (pintype "bidirectional"))
    )
    (net (code "61") (name "Net-(U4-VZCR)") (class "Default")
      (node (ref "R18") (pin "2") (pinfunction "2_2") (pintype "passive"))
      (node (ref "U4") (pin "6") (pinfunction "VZCR_6") (pintype "bidirectional"))
    )
    (net (code "62") (name "Net-(U5-PA1)") (class "Default")
      (node (ref "C21") (pin "1") (pinfunction "1_1") (pintype "bidirectional"))
      (node (ref "R20") (pin "1") (pinfunction "1_1") (pintype "passive"))
      (node (ref "U5") (pin "18") (pinfunction "PA1_18") (pintype "bidirectional"))
    )
    (net (code "63") (name "Net-(U5-PA2)") (class "Default")
      (node (ref "C20") (pin "1") (pinfunction "1_1") (pintype "bidirectional"))
      (node (ref "R18") (pin "1") (pinfunction "1_1") (pintype "passive"))
      (node (ref "U5") (pin "19") (pinfunction "PA2_19") (pintype "bidirectional"))
    )
    (net (code "64") (name "Net-(U5-PC0)") (class "Default")
      (node (ref "R14") (pin "2") (pinfunction "2_2") (pintype "passive"))
      (node (ref "U5") (pin "13") (pinfunction "PC0_13") (pintype "bidirectional"))
    )
    (net (code "65") (name "Net-(U5-PC1)") (class "Default")
      (node (ref "R13") (pin "2") (pinfunction "2_2") (pintype "passive"))
      (node (ref "U5") (pin "14") (pinfunction "PC1_14") (pintype "bidirectional"))
    )
    (net (code "66") (name "Net-(U5-PC2)") (class "Default")
      (node (ref "R12") (pin "2") (pinfunction "2_2") (pintype "passive"))
      (node (ref "U5") (pin "15") (pinfunction "PC2_15") (pintype "bidirectional"))
    )
    (net (code "67") (name "Net-(U5-PC3)") (class "Default")
      (node (ref "R11") (pin "2") (pinfunction "2_2") (pintype "passive"))
      (node (ref "U5") (pin "16") (pinfunction "PC3_16") (pintype "bidirectional"))
    )
    (net (code "68") (name "Net-(U5-PD4)") (class "Default")
      (node (ref "U5") (pin "54") (pinfunction "PD4_54") (pintype "bidirectional"))
      (node (ref "X1") (pin "1") (pinfunction "1_1") (pintype "bidirectional"))
    )
    (net (code "69") (name "Net-(U5-PD8)") (class "Default")
      (node (ref "U5") (pin "40") (pinfunction "PD8_40") (pintype "bidirectional"))
      (node (ref "X1") (pin "3") (pinfunction "3_3") (pintype "bidirectional"))
    )
    (net (code "70") (name "Net-(U5-PD9)") (class "Default")
      (node (ref "U5") (pin "41") (pinfunction "PD9_41") (pintype "bidirectional"))
      (node (ref "X1") (pin "5") (pinfunction "5_5") (pintype "bidirectional"))
    )
    (net (code "71") (name "Net-(U5-PF0-OSC_IN)") (class "Default")
      (node (ref "C19") (pin "1") (pinfunction "1_1") (pintype "bidirectional"))
      (node (ref "U5") (pin "10") (pinfunction "PF0-OSC_IN_10") (pintype "bidirectional"))
      (node (ref "Y1") (pin "1") (pinfunction "1_1") (pintype "bidirectional"))
    )
    (net (code "72") (name "Net-(U5-PF1-OSC_OUT)") (class "Default")
      (node (ref "C18") (pin "1") (pinfunction "1_1") (pintype "bidirectional"))
      (node (ref "U5") (pin "11") (pinfunction "PF1-OSC_OUT_11") (pintype "bidirectional"))
      (node (ref "Y1") (pin "3") (pinfunction "3_3") (pintype "bidirectional"))
    )
    (net (code "73") (name "VCC") (class "Default")
      (node (ref "C10") (pin "1") (pinfunction "1_1") (pintype "bidirectional"))
      (node (ref "C11") (pin "1") (pinfunction "1_1") (pintype "bidirectional"))
      (node (ref "C12") (pin "1") (pinfunction "1_1") (pintype "bidirectional"))
      (node (ref "C13") (pin "1") (pinfunction "1_1") (pintype "bidirectional"))
      (node (ref "C16") (pin "1") (pinfunction "1_1") (pintype "bidirectional"))
      (node (ref "C17") (pin "1") (pinfunction "1_1") (pintype "bidirectional"))
      (node (ref "C27") (pin "+") (pinfunction "+_+") (pintype "passive"))
      (node (ref "C3") (pin "1") (pinfunction "1_1") (pintype "bidirectional"))
      (node (ref "C6") (pin "+") (pinfunction "+_+") (pintype "passive"))
      (node (ref "C9") (pin "1") (pinfunction "1_1") (pintype "bidirectional"))
      (node (ref "D1") (pin "C") (pinfunction "C_C") (pintype "passive"))
      (node (ref "D11") (pin "A") (pinfunction "1_A") (pintype "bidirectional"))
      (node (ref "D6") (pin "A") (pinfunction "1_A") (pintype "bidirectional"))
      (node (ref "D7") (pin "A") (pinfunction "1_A") (pintype "bidirectional"))
      (node (ref "Q1") (pin "D") (pinfunction "D_D") (pintype "bidirectional"))
      (node (ref "Q2") (pin "D") (pinfunction "D_D") (pintype "bidirectional"))
      (node (ref "Q3") (pin "D") (pinfunction "D_D") (pintype "bidirectional"))
      (node (ref "R4") (pin "2") (pinfunction "2_2") (pintype "passive"))
      (node (ref "U$3") (pin "7") (pinfunction "VDD_7") (pintype "bidirectional"))
      (node (ref "U4") (pin "3") (pinfunction "IP-_3") (pintype "bidirectional"))
      (node (ref "U4") (pin "4") (pinfunction "IP-_4") (pintype "bidirectional"))
      (node (ref "U6") (pin "2") (pinfunction "VIN_2") (pintype "input"))
      (node (ref "U6") (pin "2@1") (pinfunction "VIN_2@1") (pintype "input"))
    )
    (net (code "74") (name "unconnected-(J2-SBU1-PadA8)") (class "Default")
      (node (ref "J2") (pin "A8") (pinfunction "SBU1_A8") (pintype "bidirectional"))
    )
    (net (code "75") (name "unconnected-(J2-SBU2-PadB8)") (class "Default")
      (node (ref "J2") (pin "B8") (pinfunction "SBU2_B8") (pintype "bidirectional"))
    )
    (net (code "76") (name "unconnected-(U3-CTS#-Pad5)") (class "Default")
      (node (ref "U3") (pin "5") (pinfunction "CTS#_5") (pintype "bidirectional"))
    )
    (net (code "77") (name "unconnected-(U5-PA4-Pad21)") (class "Default")
      (node (ref "U5") (pin "21") (pinfunction "PA4_21") (pintype "bidirectional"))
    )
    (net (code "78") (name "unconnected-(U5-PA5-Pad22)") (class "Default")
      (node (ref "U5") (pin "22") (pinfunction "PA5_22") (pintype "bidirectional"))
    )
    (net (code "79") (name "unconnected-(U5-PA6-Pad23)") (class "Default")
      (node (ref "U5") (pin "23") (pinfunction "PA6_23") (pintype "bidirectional"))
    )
    (net (code "80") (name "unconnected-(U5-PA11[PA9]-Pad43)") (class "Default")
      (node (ref "U5") (pin "43") (pinfunction "PA11[PA9]_43") (pintype "bidirectional"))
    )
    (net (code "81") (name "unconnected-(U5-PA12[PA10]-Pad44)") (class "Default")
      (node (ref "U5") (pin "44") (pinfunction "PA12[PA10]_44") (pintype "bidirectional"))
    )
    (net (code "82") (name "unconnected-(U5-PA15-Pad47)") (class "Default")
      (node (ref "U5") (pin "47") (pinfunction "PA15_47") (pintype "bidirectional"))
    )
    (net (code "83") (name "unconnected-(U5-PB2-Pad29)") (class "Default")
      (node (ref "U5") (pin "29") (pinfunction "PB2_29") (pintype "bidirectional"))
    )
    (net (code "84") (name "unconnected-(U5-PB3-Pad57)") (class "Default")
      (node (ref "U5") (pin "57") (pinfunction "PB3_57") (pintype "bidirectional"))
    )
    (net (code "85") (name "unconnected-(U5-PB4-Pad58)") (class "Default")
      (node (ref "U5") (pin "58") (pinfunction "PB4_58") (pintype "bidirectional"))
    )
    (net (code "86") (name "unconnected-(U5-PB5-Pad59)") (class "Default")
      (node (ref "U5") (pin "59") (pinfunction "PB5_59") (pintype "bidirectional"))
    )
    (net (code "87") (name "unconnected-(U5-PB10-Pad30)") (class "Default")
      (node (ref "U5") (pin "30") (pinfunction "PB10_30") (pintype "bidirectional"))
    )
    (net (code "88") (name "unconnected-(U5-PB11-Pad31)") (class "Default")
      (node (ref "U5") (pin "31") (pinfunction "PB11_31") (pintype "bidirectional"))
    )
    (net (code "89") (name "unconnected-(U5-PB12-Pad32)") (class "Default")
      (node (ref "U5") (pin "32") (pinfunction "PB12_32") (pintype "bidirectional"))
    )
    (net (code "90") (name "unconnected-(U5-PB15-Pad35)") (class "Default")
      (node (ref "U5") (pin "35") (pinfunction "PB15_35") (pintype "bidirectional"))
    )
    (net (code "91") (name "unconnected-(U5-PC4-Pad25)") (class "Default")
      (node (ref "U5") (pin "25") (pinfunction "PC4_25") (pintype "bidirectional"))
    )
    (net (code "92") (name "unconnected-(U5-PC5-Pad26)") (class "Default")
      (node (ref "U5") (pin "26") (pinfunction "PC5_26") (pintype "bidirectional"))
    )
    (net (code "93") (name "unconnected-(U5-PC6-Pad38)") (class "Default")
      (node (ref "U5") (pin "38") (pinfunction "PC6_38") (pintype "bidirectional"))
    )
    (net (code "94") (name "unconnected-(U5-PC7-Pad39)") (class "Default")
      (node (ref "U5") (pin "39") (pinfunction "PC7_39") (pintype "bidirectional"))
    )
    (net (code "95") (name "unconnected-(U5-PC8-Pad48)") (class "Default")
      (node (ref "U5") (pin "48") (pinfunction "PC8_48") (pintype "bidirectional"))
    )
    (net (code "96") (name "unconnected-(U5-PC9-Pad49)") (class "Default")
      (node (ref "U5") (pin "49") (pinfunction "PC9_49") (pintype "bidirectional"))
    )
    (net (code "97") (name "unconnected-(U5-PC12-Pad2)") (class "Default")
      (node (ref "U5") (pin "2") (pinfunction "PC12_2") (pintype "bidirectional"))
    )
    (net (code "98") (name "unconnected-(U5-PC14-OSC32_IN-Pad4)") (class "Default")
      (node (ref "U5") (pin "4") (pinfunction "PC14-OSC32_IN_4") (pintype "bidirectional"))
    )
    (net (code "99") (name "unconnected-(U5-PC15-OSC32_OUT-Pad5)") (class "Default")
      (node (ref "U5") (pin "5") (pinfunction "PC15-OSC32_OUT_5") (pintype "bidirectional"))
    )
    (net (code "100") (name "unconnected-(U5-PD0-Pad50)") (class "Default")
      (node (ref "U5") (pin "50") (pinfunction "PD0_50") (pintype "bidirectional"))
    )
    (net (code "101") (name "unconnected-(U5-PD1-Pad51)") (class "Default")
      (node (ref "U5") (pin "51") (pinfunction "PD1_51") (pintype "bidirectional"))
    )
    (net (code "102") (name "unconnected-(U5-PD2-Pad52)") (class "Default")
      (node (ref "U5") (pin "52") (pinfunction "PD2_52") (pintype "bidirectional"))
    )
    (net (code "103") (name "unconnected-(U5-PD3-Pad53)") (class "Default")
      (node (ref "U5") (pin "53") (pinfunction "PD3_53") (pintype "bidirectional"))
    )
  )
)
